# AVR_ISP_Pegelwandler.net
KiCad netlist of a schematic drawn in EAGLE
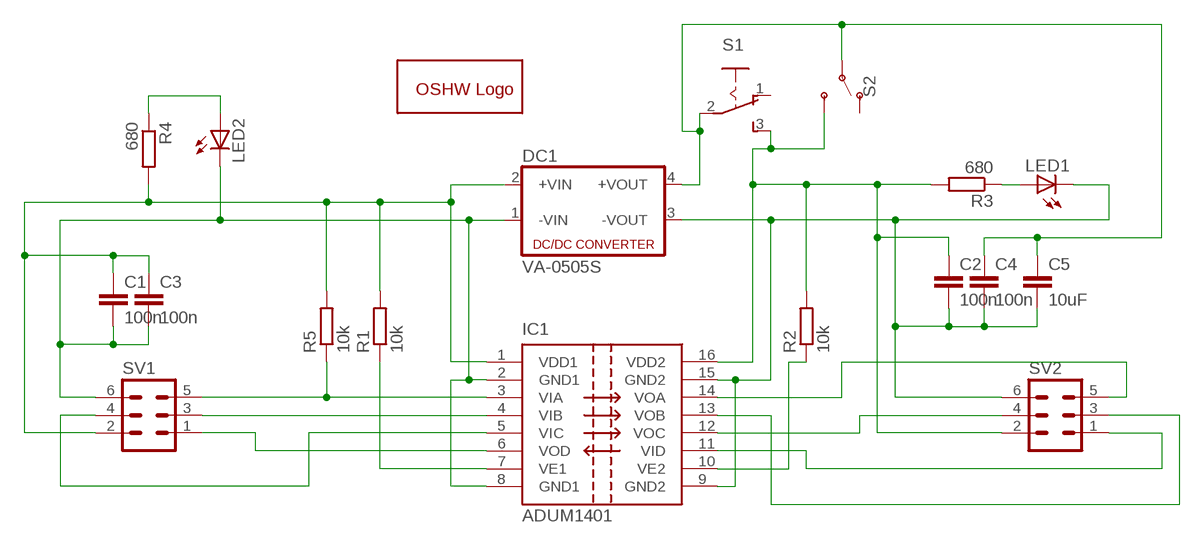
[diagram p0: schematic, sheet 1]

(export (version "E")
  (design (tool "Eeschema 10.0.6"))
  (components
    (comp (ref "C1")
      (value "100n")
      (footprint "eagle-import:C1206")
      (libsource (lib "eagle-import") (part "C-EUC1206"))
    )
    (comp (ref "C2")
      (value "100n")
      (footprint "eagle-import:C1206")
      (libsource (lib "eagle-import") (part "C-EUC1206"))
    )
    (comp (ref "C3")
      (value "100n")
      (footprint "eagle-import:C1206")
      (libsource (lib "eagle-import") (part "C-EUC1206"))
    )
    (comp (ref "C4")
      (value "100n")
      (footprint "eagle-import:C1206")
      (libsource (lib "eagle-import") (part "C-EUC1206"))
    )
    (comp (ref "C5")
      (value "10uF")
      (footprint "eagle-import:C1206")
      (libsource (lib "eagle-import") (part "C-EUC1206"))
    )
    (comp (ref "DC1")
      (value "VA-0505S")
      (footprint "eagle-import:4SIL")
      (libsource (lib "eagle-import") (part "VA-?S0505"))
    )
    (comp (ref "GOLD_ORB_SM1")
      (value "OSHWLOGOLOGO5MM")
      (footprint "eagle-import:OSHW_5MM")
      (libsource (lib "eagle-import") (part "OSHWLOGOLOGO5MM"))
    )
    (comp (ref "IC1")
      (value "ADUM1401")
      (footprint "eagle-import:SO16W")
      (libsource (lib "eagle-import") (part "ADUM1401"))
    )
    (comp (ref "LED1")
      (value "LEDCHIPLED_1206")
      (footprint "eagle-import:CHIPLED_1206")
      (libsource (lib "eagle-import") (part "LEDCHIPLED_1206"))
    )
    (comp (ref "LED2")
      (value "LEDCHIPLED_1206")
      (footprint "eagle-import:CHIPLED_1206")
      (libsource (lib "eagle-import") (part "LEDCHIPLED_1206"))
    )
    (comp (ref "R1")
      (value "10k")
      (footprint "eagle-import:R1206")
      (libsource (lib "eagle-import") (part "R-EU_R1206"))
    )
    (comp (ref "R2")
      (value "10k")
      (footprint "eagle-import:R1206")
      (libsource (lib "eagle-import") (part "R-EU_R1206"))
    )
    (comp (ref "R3")
      (value "680")
      (footprint "eagle-import:R1206")
      (libsource (lib "eagle-import") (part "R-EU_R1206"))
    )
    (comp (ref "R4")
      (value "680")
      (footprint "eagle-import:R1206")
      (libsource (lib "eagle-import") (part "R-EU_R1206"))
    )
    (comp (ref "R5")
      (value "10k")
      (footprint "eagle-import:R1206")
      (libsource (lib "eagle-import") (part "R-EU_R1206"))
    )
    (comp (ref "S1")
      (value "255SB")
      (footprint "eagle-import:255SB")
      (libsource (lib "eagle-import") (part "255SB"))
    )
    (comp (ref "S2")
      (value "SWITCH-SPDT-PTH-11.6X4.0MM")
      (footprint "eagle-import:SWITCH_SPDT_PTH_11.6X4.0MM")
      (libsource (lib "eagle-import") (part "SWITCH-SPDT-PTH-11.6X4.0MM"))
    )
    (comp (ref "SV1")
      (value "ML6")
      (footprint "eagle-import:ML6")
      (libsource (lib "eagle-import") (part "ML6"))
    )
    (comp (ref "SV2")
      (value "ML6")
      (footprint "eagle-import:ML6")
      (libsource (lib "eagle-import") (part "ML6"))
    )
  )
  (nets
    (net (code "1") (name "Net-(DC1-+VIN)") (class "Default")
      (node (ref "C1") (pin "1") (pinfunction "1_1") (pintype "passive"))
      (node (ref "C3") (pin "1") (pinfunction "1_1") (pintype "passive"))
      (node (ref "DC1") (pin "2") (pinfunction "+VIN_2") (pintype "passive"))
      (node (ref "IC1") (pin "1") (pinfunction "VDD1_1") (pintype "power_in"))
      (node (ref "R1") (pin "2") (pinfunction "2_2") (pintype "passive"))
      (node (ref "R4") (pin "2") (pinfunction "2_2") (pintype "passive"))
      (node (ref "R5") (pin "2") (pinfunction "2_2") (pintype "passive"))
      (node (ref "SV1") (pin "2") (pinfunction "2_2") (pintype "passive"))
    )
    (net (code "2") (name "Net-(DC1-+VOUT)") (class "Default")
      (node (ref "C4") (pin "1") (pinfunction "1_1") (pintype "passive"))
      (node (ref "C5") (pin "1") (pinfunction "1_1") (pintype "passive"))
      (node (ref "DC1") (pin "4") (pinfunction "+VOUT_4") (pintype "passive"))
      (node (ref "S1") (pin "2") (pinfunction "P_2") (pintype "passive"))
      (node (ref "S2") (pin "2") (pinfunction "P_2") (pintype "passive"))
    )
    (net (code "3") (name "Net-(DC1--VIN)") (class "Default")
      (node (ref "C1") (pin "2") (pinfunction "2_2") (pintype "passive"))
      (node (ref "C3") (pin "2") (pinfunction "2_2") (pintype "passive"))
      (node (ref "DC1") (pin "1") (pinfunction "-VIN_1") (pintype "passive"))
      (node (ref "IC1") (pin "2") (pinfunction "GND1_2") (pintype "power_in"))
      (node (ref "IC1") (pin "8") (pinfunction "GND1_8") (pintype "power_in"))
      (node (ref "LED2") (pin "C") (pinfunction "C_C") (pintype "passive"))
      (node (ref "SV1") (pin "6") (pinfunction "6_6") (pintype "passive"))
    )
    (net (code "4") (name "Net-(DC1--VOUT)") (class "Default")
      (node (ref "C2") (pin "2") (pinfunction "2_2") (pintype "passive"))
      (node (ref "C4") (pin "2") (pinfunction "2_2") (pintype "passive"))
      (node (ref "C5") (pin "2") (pinfunction "2_2") (pintype "passive"))
      (node (ref "DC1") (pin "3") (pinfunction "-VOUT_3") (pintype "passive"))
      (node (ref "IC1") (pin "15") (pinfunction "GND2_15") (pintype "power_in"))
      (node (ref "IC1") (pin "9") (pinfunction "GND2_9") (pintype "power_in"))
      (node (ref "LED1") (pin "C") (pinfunction "C_C") (pintype "passive"))
      (node (ref "SV2") (pin "6") (pinfunction "6_6") (pintype "passive"))
    )
    (net (code "5") (name "Net-(IC1-VDD2)") (class "Default")
      (node (ref "C2") (pin "1") (pinfunction "1_1") (pintype "passive"))
      (node (ref "IC1") (pin "16") (pinfunction "VDD2_16") (pintype "power_in"))
      (node (ref "R2") (pin "2") (pinfunction "2_2") (pintype "passive"))
      (node (ref "R3") (pin "2") (pinfunction "2_2") (pintype "passive"))
      (node (ref "S1") (pin "3") (pinfunction "S_3") (pintype "passive"))
      (node (ref "S2") (pin "3") (pinfunction "S_3") (pintype "passive"))
      (node (ref "SV2") (pin "2") (pinfunction "2_2") (pintype "passive"))
    )
    (net (code "6") (name "Net-(IC1-VE1)") (class "Default")
      (node (ref "IC1") (pin "7") (pinfunction "VE1_7") (pintype "passive"))
      (node (ref "R1") (pin "1") (pinfunction "1_1") (pintype "passive"))
    )
    (net (code "7") (name "Net-(IC1-VE2)") (class "Default")
      (node (ref "IC1") (pin "10") (pinfunction "VE2_10") (pintype "passive"))
      (node (ref "R2") (pin "1") (pinfunction "1_1") (pintype "passive"))
    )
    (net (code "8") (name "Net-(IC1-VIA)") (class "Default")
      (node (ref "IC1") (pin "3") (pinfunction "VIA_3") (pintype "input"))
      (node (ref "R5") (pin "1") (pinfunction "1_1") (pintype "passive"))
      (node (ref "SV1") (pin "5") (pinfunction "5_5") (pintype "passive"))
    )
    (net (code "9") (name "Net-(IC1-VIB)") (class "Default")
      (node (ref "IC1") (pin "4") (pinfunction "VIB_4") (pintype "input"))
      (node (ref "SV1") (pin "3") (pinfunction "3_3") (pintype "passive"))
    )
    (net (code "10") (name "Net-(IC1-VIC)") (class "Default")
      (node (ref "IC1") (pin "5") (pinfunction "VIC_5") (pintype "input"))
      (node (ref "SV1") (pin "4") (pinfunction "4_4") (pintype "passive"))
    )
    (net (code "11") (name "Net-(IC1-VID)") (class "Default")
      (node (ref "IC1") (pin "11") (pinfunction "VID_11") (pintype "input"))
      (node (ref "SV2") (pin "1") (pinfunction "1_1") (pintype "passive"))
    )
    (net (code "12") (name "Net-(IC1-VOA)") (class "Default")
      (node (ref "IC1") (pin "14") (pinfunction "VOA_14") (pintype "output"))
      (node (ref "SV2") (pin "5") (pinfunction "5_5") (pintype "passive"))
    )
    (net (code "13") (name "Net-(IC1-VOB)") (class "Default")
      (node (ref "IC1") (pin "13") (pinfunction "VOB_13") (pintype "output"))
      (node (ref "SV2") (pin "3") (pinfunction "3_3") (pintype "passive"))
    )
    (net (code "14") (name "Net-(IC1-VOC)") (class "Default")
      (node (ref "IC1") (pin "12") (pinfunction "VOC_12") (pintype "output"))
      (node (ref "SV2") (pin "4") (pinfunction "4_4") (pintype "passive"))
    )
    (net (code "15") (name "Net-(IC1-VOD)") (class "Default")
      (node (ref "IC1") (pin "6") (pinfunction "VOD_6") (pintype "output"))
      (node (ref "SV1") (pin "1") (pinfunction "1_1") (pintype "passive"))
    )
    (net (code "16") (name "Net-(LED1-PadA)") (class "Default")
      (node (ref "LED1") (pin "A") (pinfunction "A_A") (pintype "passive"))
      (node (ref "R3") (pin "1") (pinfunction "1_1") (pintype "passive"))
    )
    (net (code "17") (name "Net-(LED2-PadA)") (class "Default")
      (node (ref "LED2") (pin "A") (pinfunction "A_A") (pintype "passive"))
      (node (ref "R4") (pin "1") (pinfunction "1_1") (pintype "passive"))
    )
    (net (code "18") (name "unconnected-(S1-O-Pad1)") (class "Default")
      (node (ref "S1") (pin "1") (pinfunction "O_1") (pintype "passive"))
    )
    (net (code "19") (name "unconnected-(S2-O-Pad1)") (class "Default")
      (node (ref "S2") (pin "1") (pinfunction "O_1") (pintype "passive"))
    )
  )
)
